# hamilton-thermostat-interface.net
KiCad netlist of a schematic drawn in EAGLE
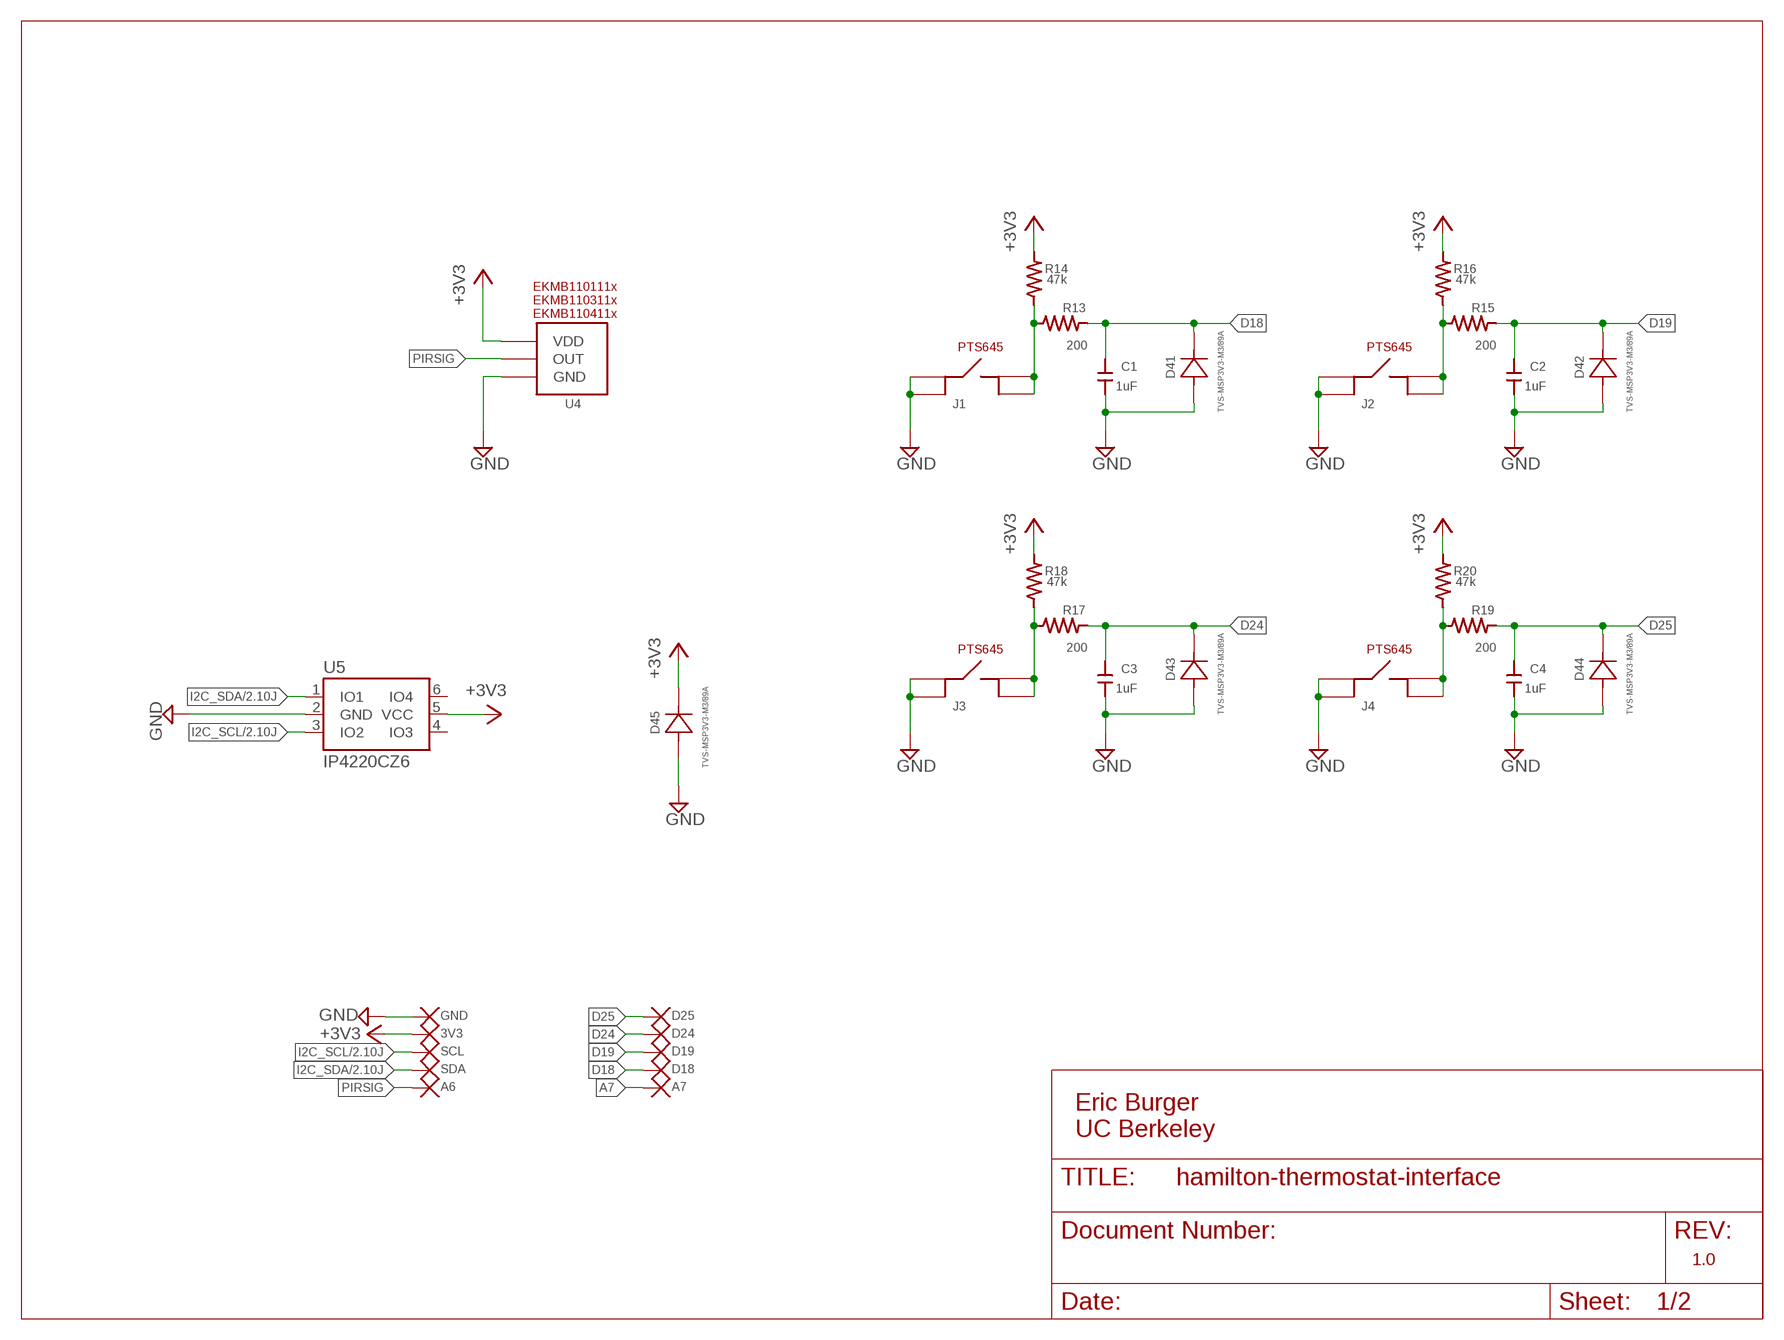
[diagram p0: schematic, sheet 1]
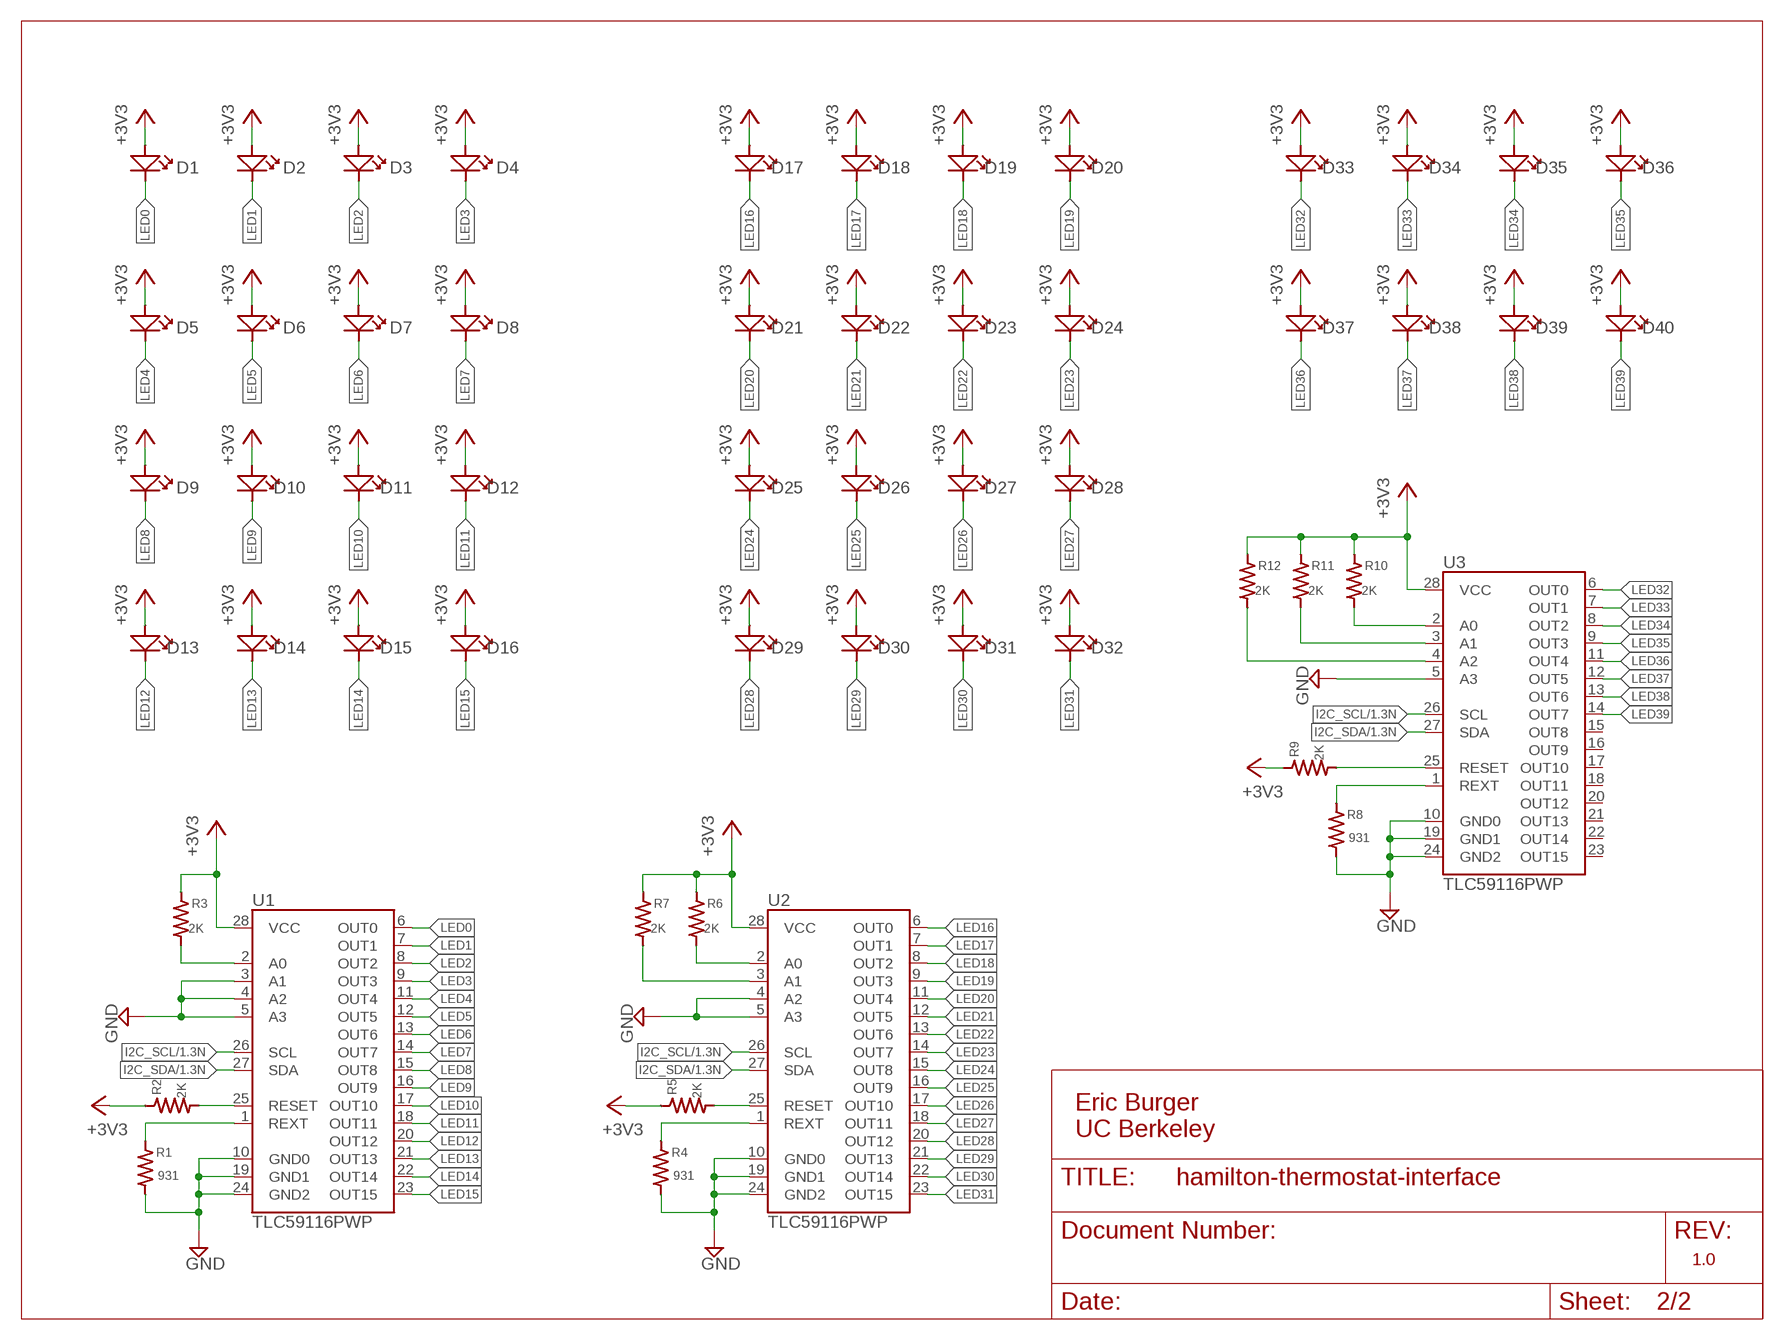
[diagram p1: schematic, sheet 2]

(export (version "E")
  (design (tool "Eeschema 10.0.6"))
  (components
    (comp (ref "C1")
      (value "1uF")
      (footprint "eagle-import:S0402")
      (libsource (lib "eagle-import") (part "0603_CAPACITORSMALL"))
    )
    (comp (ref "C2")
      (value "1uF")
      (footprint "eagle-import:S0402")
      (libsource (lib "eagle-import") (part "0603_CAPACITORSMALL"))
    )
    (comp (ref "C3")
      (value "1uF")
      (footprint "eagle-import:S0402")
      (libsource (lib "eagle-import") (part "0603_CAPACITORSMALL"))
    )
    (comp (ref "C4")
      (value "1uF")
      (footprint "eagle-import:S0402")
      (libsource (lib "eagle-import") (part "0603_CAPACITORSMALL"))
    )
    (comp (ref "D41")
      (value "TVS-MSP3V3-M3/89A")
      (footprint "eagle-import:DIODE_MSP3V3")
      (fields (field (name "MANUFACTURER_PART_NUMBER") "MSP3V3M389A"))
      (libsource (lib "eagle-import") (part "MSP3V3-M3/89A"))
    )
    (comp (ref "D42")
      (value "TVS-MSP3V3-M3/89A")
      (footprint "eagle-import:DIODE_MSP3V3")
      (fields (field (name "MANUFACTURER_PART_NUMBER") "MSP3V3M389A"))
      (libsource (lib "eagle-import") (part "MSP3V3-M3/89A"))
    )
    (comp (ref "D43")
      (value "TVS-MSP3V3-M3/89A")
      (footprint "eagle-import:DIODE_MSP3V3")
      (fields (field (name "MANUFACTURER_PART_NUMBER") "MSP3V3M389A"))
      (libsource (lib "eagle-import") (part "MSP3V3-M3/89A"))
    )
    (comp (ref "D44")
      (value "TVS-MSP3V3-M3/89A")
      (footprint "eagle-import:DIODE_MSP3V3")
      (fields (field (name "MANUFACTURER_PART_NUMBER") "MSP3V3M389A"))
      (libsource (lib "eagle-import") (part "MSP3V3-M3/89A"))
    )
    (comp (ref "D45")
      (value "TVS-MSP3V3-M3/89A")
      (footprint "eagle-import:DIODE_MSP3V3")
      (fields (field (name "MANUFACTURER_PART_NUMBER") "MSP3V3M389A"))
      (libsource (lib "eagle-import") (part "MSP3V3-M3/89A"))
    )
    (comp (ref "J1")
      (value "PTS645")
      (footprint "eagle-import:PTS645")
      (libsource (lib "eagle-import") (part "PTS645"))
    )
    (comp (ref "J2")
      (value "PTS645")
      (footprint "eagle-import:PTS645")
      (libsource (lib "eagle-import") (part "PTS645"))
    )
    (comp (ref "J3")
      (value "PTS645")
      (footprint "eagle-import:PTS645")
      (libsource (lib "eagle-import") (part "PTS645"))
    )
    (comp (ref "J4")
      (value "PTS645")
      (footprint "eagle-import:PTS645")
      (libsource (lib "eagle-import") (part "PTS645"))
    )
    (comp (ref "R13")
      (value "200")
      (footprint "eagle-import:S0402")
      (libsource (lib "eagle-import") (part "0603_RESISTORSMALL"))
    )
    (comp (ref "R14")
      (value "47k")
      (footprint "eagle-import:S0402")
      (libsource (lib "eagle-import") (part "0603_RESISTORSMALL"))
    )
    (comp (ref "R15")
      (value "200")
      (footprint "eagle-import:S0402")
      (libsource (lib "eagle-import") (part "0603_RESISTORSMALL"))
    )
    (comp (ref "R16")
      (value "47k")
      (footprint "eagle-import:S0402")
      (libsource (lib "eagle-import") (part "0603_RESISTORSMALL"))
    )
    (comp (ref "R17")
      (value "200")
      (footprint "eagle-import:S0402")
      (libsource (lib "eagle-import") (part "0603_RESISTORSMALL"))
    )
    (comp (ref "R18")
      (value "47k")
      (footprint "eagle-import:S0402")
      (libsource (lib "eagle-import") (part "0603_RESISTORSMALL"))
    )
    (comp (ref "R19")
      (value "200")
      (footprint "eagle-import:S0402")
      (libsource (lib "eagle-import") (part "0603_RESISTORSMALL"))
    )
    (comp (ref "R20")
      (value "47k")
      (footprint "eagle-import:S0402")
      (libsource (lib "eagle-import") (part "0603_RESISTORSMALL"))
    )
    (comp (ref "TP9")
      (value "SDA")
      (footprint "eagle-import:TPP")
      (libsource (lib "eagle-import") (part "TP"))
    )
    (comp (ref "TP10")
      (value "SCL")
      (footprint "eagle-import:TPP")
      (libsource (lib "eagle-import") (part "TP"))
    )
    (comp (ref "TP11")
      (value "3V3")
      (footprint "eagle-import:TPP")
      (libsource (lib "eagle-import") (part "TP"))
    )
    (comp (ref "TP12")
      (value "GND")
      (footprint "eagle-import:TPP")
      (libsource (lib "eagle-import") (part "TP"))
    )
    (comp (ref "TP14")
      (value "D25")
      (footprint "eagle-import:TPP")
      (libsource (lib "eagle-import") (part "TP"))
    )
    (comp (ref "TP15")
      (value "D24")
      (footprint "eagle-import:TPP")
      (libsource (lib "eagle-import") (part "TP"))
    )
    (comp (ref "TP16")
      (value "A6")
      (footprint "eagle-import:TPP")
      (libsource (lib "eagle-import") (part "TP"))
    )
    (comp (ref "TP17")
      (value "D18")
      (footprint "eagle-import:TPP")
      (libsource (lib "eagle-import") (part "TP"))
    )
    (comp (ref "TP18")
      (value "D19")
      (footprint "eagle-import:TPP")
      (libsource (lib "eagle-import") (part "TP"))
    )
    (comp (ref "TP19")
      (value "A7")
      (footprint "eagle-import:TPP")
      (libsource (lib "eagle-import") (part "TP"))
    )
    (comp (ref "U4")
      (value "PANASONIC_PIR")
      (footprint "eagle-import:PIR")
      (libsource (lib "eagle-import") (part "PANASONIC_PIR"))
    )
    (comp (ref "U5")
      (value "IP4220CZ6")
      (footprint "eagle-import:SOT23-6")
      (libsource (lib "eagle-import") (part "IP4220CZ6SOT-23"))
    )
    (comp (ref "D1")
      (value "DNP")
      (footprint "eagle-import:LINE_0603")
      (libsource (lib "eagle-import") (part "STATLEDLINE"))
    )
    (comp (ref "D2")
      (value "DNP")
      (footprint "eagle-import:LINE_0603")
      (libsource (lib "eagle-import") (part "STATLEDLINE"))
    )
    (comp (ref "D3")
      (value "DNP")
      (footprint "eagle-import:LINE_0603")
      (libsource (lib "eagle-import") (part "STATLEDLINE"))
    )
    (comp (ref "D4")
      (value "DNP")
      (footprint "eagle-import:LINE_0603")
      (libsource (lib "eagle-import") (part "STATLEDLINE"))
    )
    (comp (ref "D5")
      (value "DNP")
      (footprint "eagle-import:LINE_0603")
      (libsource (lib "eagle-import") (part "STATLEDLINE"))
    )
    (comp (ref "D6")
      (value "DNP")
      (footprint "eagle-import:LINE_0603")
      (libsource (lib "eagle-import") (part "STATLEDLINE"))
    )
    (comp (ref "D7")
      (value "DNP")
      (footprint "eagle-import:LINE_0603")
      (libsource (lib "eagle-import") (part "STATLEDLINE"))
    )
    (comp (ref "D8")
      (value "DNP")
      (footprint "eagle-import:LINE_0603")
      (libsource (lib "eagle-import") (part "STATLEDLINE"))
    )
    (comp (ref "D9")
      (value "DNP")
      (footprint "eagle-import:LINE_0603")
      (libsource (lib "eagle-import") (part "STATLEDLINE"))
    )
    (comp (ref "D10")
      (value "DNP")
      (footprint "eagle-import:LINE_0603")
      (libsource (lib "eagle-import") (part "STATLEDLINE"))
    )
    (comp (ref "D11")
      (value "DNP")
      (footprint "eagle-import:LINE_0603")
      (libsource (lib "eagle-import") (part "STATLEDLINE"))
    )
    (comp (ref "D12")
      (value "DNP")
      (footprint "eagle-import:LINE_0603")
      (libsource (lib "eagle-import") (part "STATLEDLINE"))
    )
    (comp (ref "D13")
      (value "DNP")
      (footprint "eagle-import:LINE_0603")
      (libsource (lib "eagle-import") (part "STATLEDLINE"))
    )
    (comp (ref "D14")
      (value "DNP")
      (footprint "eagle-import:LINE_0603")
      (libsource (lib "eagle-import") (part "STATLEDLINE"))
    )
    (comp (ref "D15")
      (value "DNP")
      (footprint "eagle-import:LINE_0603")
      (libsource (lib "eagle-import") (part "STATLEDLINE"))
    )
    (comp (ref "D16")
      (value "DNP")
      (footprint "eagle-import:LINE_0603")
      (libsource (lib "eagle-import") (part "STATLEDLINE"))
    )
    (comp (ref "D17")
      (value "DNP")
      (footprint "eagle-import:LINE_0603")
      (libsource (lib "eagle-import") (part "STATLEDLINE"))
    )
    (comp (ref "D18")
      (value "DNP")
      (footprint "eagle-import:LINE_0603")
      (libsource (lib "eagle-import") (part "STATLEDLINE"))
    )
    (comp (ref "D19")
      (value "DNP")
      (footprint "eagle-import:LINE_0603")
      (libsource (lib "eagle-import") (part "STATLEDLINE"))
    )
    (comp (ref "D20")
      (value "DNP")
      (footprint "eagle-import:LINE_0603")
      (libsource (lib "eagle-import") (part "STATLEDLINE"))
    )
    (comp (ref "D21")
      (value "DNP")
      (footprint "eagle-import:LINE_0603")
      (libsource (lib "eagle-import") (part "STATLEDLINE"))
    )
    (comp (ref "D22")
      (value "DNP")
      (footprint "eagle-import:LINE_0603")
      (libsource (lib "eagle-import") (part "STATLEDLINE"))
    )
    (comp (ref "D23")
      (value "DNP")
      (footprint "eagle-import:LINE_0603")
      (libsource (lib "eagle-import") (part "STATLEDLINE"))
    )
    (comp (ref "D24")
      (value "DNP")
      (footprint "eagle-import:LINE_0603")
      (libsource (lib "eagle-import") (part "STATLEDLINE"))
    )
    (comp (ref "D25")
      (value "DNP")
      (footprint "eagle-import:LINE_0603")
      (libsource (lib "eagle-import") (part "STATLEDLINE"))
    )
    (comp (ref "D26")
      (value "DNP")
      (footprint "eagle-import:LINE_0603")
      (libsource (lib "eagle-import") (part "STATLEDLINE"))
    )
    (comp (ref "D27")
      (value "DNP")
      (footprint "eagle-import:LINE_0603")
      (libsource (lib "eagle-import") (part "STATLEDLINE"))
    )
    (comp (ref "D28")
      (value "DNP")
      (footprint "eagle-import:LINE_0603")
      (libsource (lib "eagle-import") (part "STATLEDLINE"))
    )
    (comp (ref "D29")
      (value "DNP")
      (footprint "eagle-import:LINE_0603")
      (libsource (lib "eagle-import") (part "STATLEDLINE"))
    )
    (comp (ref "D30")
      (value "DNP")
      (footprint "eagle-import:LINE_0603")
      (libsource (lib "eagle-import") (part "STATLEDLINE"))
    )
    (comp (ref "D31")
      (value "DNP")
      (footprint "eagle-import:LINE_0603")
      (libsource (lib "eagle-import") (part "STATLEDLINE"))
    )
    (comp (ref "D32")
      (value "DNP")
      (footprint "eagle-import:LINE_0603")
      (libsource (lib "eagle-import") (part "STATLEDLINE"))
    )
    (comp (ref "D33")
      (value "DNP")
      (footprint "eagle-import:LINE_0603")
      (libsource (lib "eagle-import") (part "STATLEDLINE"))
    )
    (comp (ref "D34")
      (value "DNP")
      (footprint "eagle-import:LINE_0603")
      (libsource (lib "eagle-import") (part "STATLEDLINE"))
    )
    (comp (ref "D35")
      (value "DNP")
      (footprint "eagle-import:LINE_0603")
      (libsource (lib "eagle-import") (part "STATLEDLINE"))
    )
    (comp (ref "D36")
      (value "DNP")
      (footprint "eagle-import:LINE_0603")
      (libsource (lib "eagle-import") (part "STATLEDLINE"))
    )
    (comp (ref "D37")
      (value "DNP")
      (footprint "eagle-import:LINE_0603")
      (libsource (lib "eagle-import") (part "STATLEDLINE"))
    )
    (comp (ref "D38")
      (value "DNP")
      (footprint "eagle-import:LINE_0603")
      (libsource (lib "eagle-import") (part "STATLEDLINE"))
    )
    (comp (ref "D39")
      (value "DNP")
      (footprint "eagle-import:LINE_0603")
      (libsource (lib "eagle-import") (part "STATLEDLINE"))
    )
    (comp (ref "D40")
      (value "DNP")
      (footprint "eagle-import:LINE_0603")
      (libsource (lib "eagle-import") (part "STATLEDLINE"))
    )
    (comp (ref "R1")
      (value "931")
      (footprint "eagle-import:S0402")
      (libsource (lib "eagle-import") (part "0603_RESISTORSMALL"))
    )
    (comp (ref "R2")
      (value "2K")
      (footprint "eagle-import:S0402")
      (libsource (lib "eagle-import") (part "0603_RESISTORSMALL"))
    )
    (comp (ref "R3")
      (value "2K")
      (footprint "eagle-import:S0402")
      (libsource (lib "eagle-import") (part "0603_RESISTORSMALL"))
    )
    (comp (ref "R4")
      (value "931")
      (footprint "eagle-import:S0402")
      (libsource (lib "eagle-import") (part "0603_RESISTORSMALL"))
    )
    (comp (ref "R5")
      (value "2K")
      (footprint "eagle-import:S0402")
      (libsource (lib "eagle-import") (part "0603_RESISTORSMALL"))
    )
    (comp (ref "R6")
      (value "2K")
      (footprint "eagle-import:S0402")
      (libsource (lib "eagle-import") (part "0603_RESISTORSMALL"))
    )
    (comp (ref "R7")
      (value "2K")
      (footprint "eagle-import:S0402")
      (libsource (lib "eagle-import") (part "0603_RESISTORSMALL"))
    )
    (comp (ref "R8")
      (value "931")
      (footprint "eagle-import:S0402")
      (libsource (lib "eagle-import") (part "0603_RESISTORSMALL"))
    )
    (comp (ref "R9")
      (value "2K")
      (footprint "eagle-import:S0402")
      (libsource (lib "eagle-import") (part "0603_RESISTORSMALL"))
    )
    (comp (ref "R10")
      (value "2K")
      (footprint "eagle-import:S0402")
      (libsource (lib "eagle-import") (part "0603_RESISTORSMALL"))
    )
    (comp (ref "R11")
      (value "2K")
      (footprint "eagle-import:S0402")
      (libsource (lib "eagle-import") (part "0603_RESISTORSMALL"))
    )
    (comp (ref "R12")
      (value "2K")
      (footprint "eagle-import:S0402")
      (libsource (lib "eagle-import") (part "0603_RESISTORSMALL"))
    )
    (comp (ref "U1")
      (value "TLC59116PWP")
      (footprint "eagle-import:TSSOP28-GROUNDPAD")
      (libsource (lib "eagle-import") (part "TLC59116PWP"))
    )
    (comp (ref "U2")
      (value "TLC59116PWP")
      (footprint "eagle-import:TSSOP28-GROUNDPAD")
      (libsource (lib "eagle-import") (part "TLC59116PWP"))
    )
    (comp (ref "U3")
      (value "TLC59116PWP")
      (footprint "eagle-import:TSSOP28-GROUNDPAD")
      (libsource (lib "eagle-import") (part "TLC59116PWP"))
    )
  )
  (nets
    (net (code "1") (name "+3V3") (class "Default")
      (node (ref "D1") (pin "P") (pinfunction "+_P") (pintype "passive"))
      (node (ref "D10") (pin "P") (pinfunction "+_P") (pintype "passive"))
      (node (ref "D11") (pin "P") (pinfunction "+_P") (pintype "passive"))
      (node (ref "D12") (pin "P") (pinfunction "+_P") (pintype "passive"))
      (node (ref "D13") (pin "P") (pinfunction "+_P") (pintype "passive"))
      (node (ref "D14") (pin "P") (pinfunction "+_P") (pintype "passive"))
      (node (ref "D15") (pin "P") (pinfunction "+_P") (pintype "passive"))
      (node (ref "D16") (pin "P") (pinfunction "+_P") (pintype "passive"))
      (node (ref "D17") (pin "P") (pinfunction "+_P") (pintype "passive"))
      (node (ref "D18") (pin "P") (pinfunction "+_P") (pintype "passive"))
      (node (ref "D19") (pin "P") (pinfunction "+_P") (pintype "passive"))
      (node (ref "D2") (pin "P") (pinfunction "+_P") (pintype "passive"))
      (node (ref "D20") (pin "P") (pinfunction "+_P") (pintype "passive"))
      (node (ref "D21") (pin "P") (pinfunction "+_P") (pintype "passive"))
      (node (ref "D22") (pin "P") (pinfunction "+_P") (pintype "passive"))
      (node (ref "D23") (pin "P") (pinfunction "+_P") (pintype "passive"))
      (node (ref "D24") (pin "P") (pinfunction "+_P") (pintype "passive"))
      (node (ref "D25") (pin "P") (pinfunction "+_P") (pintype "passive"))
      (node (ref "D26") (pin "P") (pinfunction "+_P") (pintype "passive"))
      (node (ref "D27") (pin "P") (pinfunction "+_P") (pintype "passive"))
      (node (ref "D28") (pin "P") (pinfunction "+_P") (pintype "passive"))
      (node (ref "D29") (pin "P") (pinfunction "+_P") (pintype "passive"))
      (node (ref "D3") (pin "P") (pinfunction "+_P") (pintype "passive"))
      (node (ref "D30") (pin "P") (pinfunction "+_P") (pintype "passive"))
      (node (ref "D31") (pin "P") (pinfunction "+_P") (pintype "passive"))
      (node (ref "D32") (pin "P") (pinfunction "+_P") (pintype "passive"))
      (node (ref "D33") (pin "P") (pinfunction "+_P") (pintype "passive"))
      (node (ref "D34") (pin "P") (pinfunction "+_P") (pintype "passive"))
      (node (ref "D35") (pin "P") (pinfunction "+_P") (pintype "passive"))
      (node (ref "D36") (pin "P") (pinfunction "+_P") (pintype "passive"))
      (node (ref "D37") (pin "P") (pinfunction "+_P") (pintype "passive"))
      (node (ref "D38") (pin "P") (pinfunction "+_P") (pintype "passive"))
      (node (ref "D39") (pin "P") (pinfunction "+_P") (pintype "passive"))
      (node (ref "D4") (pin "P") (pinfunction "+_P") (pintype "passive"))
      (node (ref "D40") (pin "P") (pinfunction "+_P") (pintype "passive"))
      (node (ref "D45") (pin "1") (pinfunction "12_1") (pintype "passive"))
      (node (ref "D5") (pin "P") (pinfunction "+_P") (pintype "passive"))
      (node (ref "D6") (pin "P") (pinfunction "+_P") (pintype "passive"))
      (node (ref "D7") (pin "P") (pinfunction "+_P") (pintype "passive"))
      (node (ref "D8") (pin "P") (pinfunction "+_P") (pintype "passive"))
      (node (ref "D9") (pin "P") (pinfunction "+_P") (pintype "passive"))
      (node (ref "R10") (pin "P$2") (pinfunction "P$2_P$2") (pintype "passive"))
      (node (ref "R11") (pin "P$2") (pinfunction "P$2_P$2") (pintype "passive"))
      (node (ref "R12") (pin "P$2") (pinfunction "P$2_P$2") (pintype "passive"))
      (node (ref "R14") (pin "P$1") (pinfunction "P$1_P$1") (pintype "passive"))
      (node (ref "R16") (pin "P$1") (pinfunction "P$1_P$1") (pintype "passive"))
      (node (ref "R18") (pin "P$1") (pinfunction "P$1_P$1") (pintype "passive"))
      (node (ref "R2") (pin "P$2") (pinfunction "P$2_P$2") (pintype "passive"))
      (node (ref "R20") (pin "P$1") (pinfunction "P$1_P$1") (pintype "passive"))
      (node (ref "R3") (pin "P$2") (pinfunction "P$2_P$2") (pintype "passive"))
      (node (ref "R5") (pin "P$2") (pinfunction "P$2_P$2") (pintype "passive"))
      (node (ref "R6") (pin "P$2") (pinfunction "P$2_P$2") (pintype "passive"))
      (node (ref "R7") (pin "P$2") (pinfunction "P$2_P$2") (pintype "passive"))
      (node (ref "R9") (pin "P$2") (pinfunction "P$2_P$2") (pintype "passive"))
      (node (ref "TP11") (pin "P$1") (pinfunction "P$1_P$1") (pintype "bidirectional"))
      (node (ref "U1") (pin "28") (pinfunction "VCC_28") (pintype "bidirectional"))
      (node (ref "U2") (pin "28") (pinfunction "VCC_28") (pintype "bidirectional"))
      (node (ref "U3") (pin "28") (pinfunction "VCC_28") (pintype "bidirectional"))
      (node (ref "U4") (pin "VDD") (pinfunction "VDD_VDD") (pintype "bidirectional"))
      (node (ref "U5") (pin "5") (pinfunction "VCC_5") (pintype "bidirectional"))
    )
    (net (code "2") (name "A7") (class "Default")
      (node (ref "TP19") (pin "P$1") (pinfunction "P$1_P$1") (pintype "bidirectional"))
    )
    (net (code "3") (name "D18") (class "Default")
      (node (ref "C1") (pin "P$2") (pinfunction "P$2_P$2") (pintype "passive"))
      (node (ref "D41") (pin "1") (pinfunction "12_1") (pintype "passive"))
      (node (ref "R13") (pin "P$1") (pinfunction "P$1_P$1") (pintype "passive"))
      (node (ref "TP17") (pin "P$1") (pinfunction "P$1_P$1") (pintype "bidirectional"))
    )
    (net (code "4") (name "D19") (class "Default")
      (node (ref "C2") (pin "P$2") (pinfunction "P$2_P$2") (pintype "passive"))
      (node (ref "D42") (pin "1") (pinfunction "12_1") (pintype "passive"))
      (node (ref "R15") (pin "P$1") (pinfunction "P$1_P$1") (pintype "passive"))
      (node (ref "TP18") (pin "P$1") (pinfunction "P$1_P$1") (pintype "bidirectional"))
    )
    (net (code "5") (name "D24") (class "Default")
      (node (ref "C3") (pin "P$2") (pinfunction "P$2_P$2") (pintype "passive"))
      (node (ref "D43") (pin "1") (pinfunction "12_1") (pintype "passive"))
      (node (ref "R17") (pin "P$1") (pinfunction "P$1_P$1") (pintype "passive"))
      (node (ref "TP15") (pin "P$1") (pinfunction "P$1_P$1") (pintype "bidirectional"))
    )
    (net (code "6") (name "D25") (class "Default")
      (node (ref "C4") (pin "P$2") (pinfunction "P$2_P$2") (pintype "passive"))
      (node (ref "D44") (pin "1") (pinfunction "12_1") (pintype "passive"))
      (node (ref "R19") (pin "P$1") (pinfunction "P$1_P$1") (pintype "passive"))
      (node (ref "TP14") (pin "P$1") (pinfunction "P$1_P$1") (pintype "bidirectional"))
    )
    (net (code "7") (name "GND") (class "Default")
      (node (ref "C1") (pin "P$1") (pinfunction "P$1_P$1") (pintype "passive"))
      (node (ref "C2") (pin "P$1") (pinfunction "P$1_P$1") (pintype "passive"))
      (node (ref "C3") (pin "P$1") (pinfunction "P$1_P$1") (pintype "passive"))
      (node (ref "C4") (pin "P$1") (pinfunction "P$1_P$1") (pintype "passive"))
      (node (ref "D41") (pin "2") (pinfunction "21_2") (pintype "passive"))
      (node (ref "D42") (pin "2") (pinfunction "21_2") (pintype "passive"))
      (node (ref "D43") (pin "2") (pinfunction "21_2") (pintype "passive"))
      (node (ref "D44") (pin "2") (pinfunction "21_2") (pintype "passive"))
      (node (ref "D45") (pin "2") (pinfunction "21_2") (pintype "passive"))
      (node (ref "J1") (pin "3") (pinfunction "3_3") (pintype "bidirectional"))
      (node (ref "J1") (pin "4") (pinfunction "4_4") (pintype "bidirectional"))
      (node (ref "J2") (pin "3") (pinfunction "3_3") (pintype "bidirectional"))
      (node (ref "J2") (pin "4") (pinfunction "4_4") (pintype "bidirectional"))
      (node (ref "J3") (pin "3") (pinfunction "3_3") (pintype "bidirectional"))
      (node (ref "J3") (pin "4") (pinfunction "4_4") (pintype "bidirectional"))
      (node (ref "J4") (pin "3") (pinfunction "3_3") (pintype "bidirectional"))
      (node (ref "J4") (pin "4") (pinfunction "4_4") (pintype "bidirectional"))
      (node (ref "R1") (pin "P$1") (pinfunction "P$1_P$1") (pintype "passive"))
      (node (ref "R4") (pin "P$1") (pinfunction "P$1_P$1") (pintype "passive"))
      (node (ref "R8") (pin "P$1") (pinfunction "P$1_P$1") (pintype "passive"))
      (node (ref "TP12") (pin "P$1") (pinfunction "P$1_P$1") (pintype "bidirectional"))
      (node (ref "U1") (pin "10") (pinfunction "GND0_10") (pintype "bidirectional"))
      (node (ref "U1") (pin "19") (pinfunction "GND1_19") (pintype "bidirectional"))
      (node (ref "U1") (pin "24") (pinfunction "GND2_24") (pintype "bidirectional"))
      (node (ref "U1") (pin "3") (pinfunction "A1_3") (pintype "bidirectional"))
      (node (ref "U1") (pin "4") (pinfunction "A2_4") (pintype "bidirectional"))
      (node (ref "U1") (pin "5") (pinfunction "A3_5") (pintype "bidirectional"))
      (node (ref "U2") (pin "10") (pinfunction "GND0_10") (pintype "bidirectional"))
      (node (ref "U2") (pin "19") (pinfunction "GND1_19") (pintype "bidirectional"))
      (node (ref "U2") (pin "24") (pinfunction "GND2_24") (pintype "bidirectional"))
      (node (ref "U2") (pin "4") (pinfunction "A2_4") (pintype "bidirectional"))
      (node (ref "U2") (pin "5") (pinfunction "A3_5") (pintype "bidirectional"))
      (node (ref "U3") (pin "10") (pinfunction "GND0_10") (pintype "bidirectional"))
      (node (ref "U3") (pin "19") (pinfunction "GND1_19") (pintype "bidirectional"))
      (node (ref "U3") (pin "24") (pinfunction "GND2_24") (pintype "bidirectional"))
      (node (ref "U3") (pin "5") (pinfunction "A3_5") (pintype "bidirectional"))
      (node (ref "U4") (pin "GND") (pinfunction "GND_GND") (pintype "bidirectional"))
      (node (ref "U5") (pin "2") (pinfunction "GND_2") (pintype "bidirectional"))
    )
    (net (code "8") (name "I2C_SCL") (class "Default")
      (node (ref "TP10") (pin "P$1") (pinfunction "P$1_P$1") (pintype "bidirectional"))
      (node (ref "U1") (pin "26") (pinfunction "SCL_26") (pintype "bidirectional"))
      (node (ref "U2") (pin "26") (pinfunction "SCL_26") (pintype "bidirectional"))
      (node (ref "U3") (pin "26") (pinfunction "SCL_26") (pintype "bidirectional"))
      (node (ref "U5") (pin "3") (pinfunction "IO2_3") (pintype "bidirectional"))
    )
    (net (code "9") (name "I2C_SDA") (class "Default")
      (node (ref "TP9") (pin "P$1") (pinfunction "P$1_P$1") (pintype "bidirectional"))
      (node (ref "U1") (pin "27") (pinfunction "SDA_27") (pintype "bidirectional"))
      (node (ref "U2") (pin "27") (pinfunction "SDA_27") (pintype "bidirectional"))
      (node (ref "U3") (pin "27") (pinfunction "SDA_27") (pintype "bidirectional"))
      (node (ref "U5") (pin "1") (pinfunction "IO1_1") (pintype "bidirectional"))
    )
    (net (code "10") (name "LED0") (class "Default")
      (node (ref "D1") (pin "N") (pinfunction "-_N") (pintype "passive"))
      (node (ref "U1") (pin "6") (pinfunction "OUT0_6") (pintype "bidirectional"))
    )
    (net (code "11") (name "LED1") (class "Default")
      (node (ref "D2") (pin "N") (pinfunction "-_N") (pintype "passive"))
      (node (ref "U1") (pin "7") (pinfunction "OUT1_7") (pintype "bidirectional"))
    )
    (net (code "12") (name "LED2") (class "Default")
      (node (ref "D3") (pin "N") (pinfunction "-_N") (pintype "passive"))
      (node (ref "U1") (pin "8") (pinfunction "OUT2_8") (pintype "bidirectional"))
    )
    (net (code "13") (name "LED3") (class "Default")
      (node (ref "D4") (pin "N") (pinfunction "-_N") (pintype "passive"))
      (node (ref "U1") (pin "9") (pinfunction "OUT3_9") (pintype "bidirectional"))
    )
    (net (code "14") (name "LED4") (class "Default")
      (node (ref "D5") (pin "N") (pinfunction "-_N") (pintype "passive"))
      (node (ref "U1") (pin "11") (pinfunction "OUT4_11") (pintype "bidirectional"))
    )
    (net (code "15") (name "LED5") (class "Default")
      (node (ref "D6") (pin "N") (pinfunction "-_N") (pintype "passive"))
      (node (ref "U1") (pin "12") (pinfunction "OUT5_12") (pintype "bidirectional"))
    )
    (net (code "16") (name "LED6") (class "Default")
      (node (ref "D7") (pin "N") (pinfunction "-_N") (pintype "passive"))
      (node (ref "U1") (pin "13") (pinfunction "OUT6_13") (pintype "bidirectional"))
    )
    (net (code "17") (name "LED7") (class "Default")
      (node (ref "D8") (pin "N") (pinfunction "-_N") (pintype "passive"))
      (node (ref "U1") (pin "14") (pinfunction "OUT7_14") (pintype "bidirectional"))
    )
    (net (code "18") (name "LED8") (class "Default")
      (node (ref "D9") (pin "N") (pinfunction "-_N") (pintype "passive"))
      (node (ref "U1") (pin "15") (pinfunction "OUT8_15") (pintype "bidirectional"))
    )
    (net (code "19") (name "LED9") (class "Default")
      (node (ref "D10") (pin "N") (pinfunction "-_N") (pintype "passive"))
      (node (ref "U1") (pin "16") (pinfunction "OUT9_16") (pintype "bidirectional"))
    )
    (net (code "20") (name "LED10") (class "Default")
      (node (ref "D11") (pin "N") (pinfunction "-_N") (pintype "passive"))
      (node (ref "U1") (pin "17") (pinfunction "OUT10_17") (pintype "bidirectional"))
    )
    (net (code "21") (name "LED11") (class "Default")
      (node (ref "D12") (pin "N") (pinfunction "-_N") (pintype "passive"))
      (node (ref "U1") (pin "18") (pinfunction "OUT11_18") (pintype "bidirectional"))
    )
    (net (code "22") (name "LED12") (class "Default")
      (node (ref "D13") (pin "N") (pinfunction "-_N") (pintype "passive"))
      (node (ref "U1") (pin "20") (pinfunction "OUT12_20") (pintype "bidirectional"))
    )
    (net (code "23") (name "LED13") (class "Default")
      (node (ref "D14") (pin "N") (pinfunction "-_N") (pintype "passive"))
      (node (ref "U1") (pin "21") (pinfunction "OUT13_21") (pintype "bidirectional"))
    )
    (net (code "24") (name "LED14") (class "Default")
      (node (ref "D15") (pin "N") (pinfunction "-_N") (pintype "passive"))
      (node (ref "U1") (pin "22") (pinfunction "OUT14_22") (pintype "bidirectional"))
    )
    (net (code "25") (name "LED15") (class "Default")
      (node (ref "D16") (pin "N") (pinfunction "-_N") (pintype "passive"))
      (node (ref "U1") (pin "23") (pinfunction "OUT15_23") (pintype "bidirectional"))
    )
    (net (code "26") (name "LED16") (class "Default")
      (node (ref "D17") (pin "N") (pinfunction "-_N") (pintype "passive"))
      (node (ref "U2") (pin "6") (pinfunction "OUT0_6") (pintype "bidirectional"))
    )
    (net (code "27") (name "LED17") (class "Default")
      (node (ref "D18") (pin "N") (pinfunction "-_N") (pintype "passive"))
      (node (ref "U2") (pin "7") (pinfunction "OUT1_7") (pintype "bidirectional"))
    )
    (net (code "28") (name "LED18") (class "Default")
      (node (ref "D19") (pin "N") (pinfunction "-_N") (pintype "passive"))
      (node (ref "U2") (pin "8") (pinfunction "OUT2_8") (pintype "bidirectional"))
    )
    (net (code "29") (name "LED19") (class "Default")
      (node (ref "D20") (pin "N") (pinfunction "-_N") (pintype "passive"))
      (node (ref "U2") (pin "9") (pinfunction "OUT3_9") (pintype "bidirectional"))
    )
    (net (code "30") (name "LED20") (class "Default")
      (node (ref "D21") (pin "N") (pinfunction "-_N") (pintype "passive"))
      (node (ref "U2") (pin "11") (pinfunction "OUT4_11") (pintype "bidirectional"))
    )
    (net (code "31") (name "LED21") (class "Default")
      (node (ref "D22") (pin "N") (pinfunction "-_N") (pintype "passive"))
      (node (ref "U2") (pin "12") (pinfunction "OUT5_12") (pintype "bidirectional"))
    )
    (net (code "32") (name "LED22") (class "Default")
      (node (ref "D23") (pin "N") (pinfunction "-_N") (pintype "passive"))
      (node (ref "U2") (pin "13") (pinfunction "OUT6_13") (pintype "bidirectional"))
    )
    (net (code "33") (name "LED23") (class "Default")
      (node (ref "D24") (pin "N") (pinfunction "-_N") (pintype "passive"))
      (node (ref "U2") (pin "14") (pinfunction "OUT7_14") (pintype "bidirectional"))
    )
    (net (code "34") (name "LED24") (class "Default")
      (node (ref "D25") (pin "N") (pinfunction "-_N") (pintype "passive"))
      (node (ref "U2") (pin "15") (pinfunction "OUT8_15") (pintype "bidirectional"))
    )
    (net (code "35") (name "LED25") (class "Default")
      (node (ref "D26") (pin "N") (pinfunction "-_N") (pintype "passive"))
      (node (ref "U2") (pin "16") (pinfunction "OUT9_16") (pintype "bidirectional"))
    )
    (net (code "36") (name "LED26") (class "Default")
      (node (ref "D27") (pin "N") (pinfunction "-_N") (pintype "passive"))
      (node (ref "U2") (pin "17") (pinfunction "OUT10_17") (pintype "bidirectional"))
    )
    (net (code "37") (name "LED27") (class "Default")
      (node (ref "D28") (pin "N") (pinfunction "-_N") (pintype "passive"))
      (node (ref "U2") (pin "18") (pinfunction "OUT11_18") (pintype "bidirectional"))
    )
    (net (code "38") (name "LED28") (class "Default")
      (node (ref "D29") (pin "N") (pinfunction "-_N") (pintype "passive"))
      (node (ref "U2") (pin "20") (pinfunction "OUT12_20") (pintype "bidirectional"))
    )
    (net (code "39") (name "LED29") (class "Default")
      (node (ref "D30") (pin "N") (pinfunction "-_N") (pintype "passive"))
      (node (ref "U2") (pin "21") (pinfunction "OUT13_21") (pintype "bidirectional"))
    )
    (net (code "40") (name "LED30") (class "Default")
      (node (ref "D31") (pin "N") (pinfunction "-_N") (pintype "passive"))
      (node (ref "U2") (pin "22") (pinfunction "OUT14_22") (pintype "bidirectional"))
    )
    (net (code "41") (name "LED31") (class "Default")
      (node (ref "D32") (pin "N") (pinfunction "-_N") (pintype "passive"))
      (node (ref "U2") (pin "23") (pinfunction "OUT15_23") (pintype "bidirectional"))
    )
    (net (code "42") (name "LED32") (class "Default")
      (node (ref "D33") (pin "N") (pinfunction "-_N") (pintype "passive"))
      (node (ref "U3") (pin "6") (pinfunction "OUT0_6") (pintype "bidirectional"))
    )
    (net (code "43") (name "LED33") (class "Default")
      (node (ref "D34") (pin "N") (pinfunction "-_N") (pintype "passive"))
      (node (ref "U3") (pin "7") (pinfunction "OUT1_7") (pintype "bidirectional"))
    )
    (net (code "44") (name "LED34") (class "Default")
      (node (ref "D35") (pin "N") (pinfunction "-_N") (pintype "passive"))
      (node (ref "U3") (pin "8") (pinfunction "OUT2_8") (pintype "bidirectional"))
    )
    (net (code "45") (name "LED35") (class "Default")
      (node (ref "D36") (pin "N") (pinfunction "-_N") (pintype "passive"))
      (node (ref "U3") (pin "9") (pinfunction "OUT3_9") (pintype "bidirectional"))
    )
    (net (code "46") (name "LED36") (class "Default")
      (node (ref "D37") (pin "N") (pinfunction "-_N") (pintype "passive"))
      (node (ref "U3") (pin "11") (pinfunction "OUT4_11") (pintype "bidirectional"))
    )
    (net (code "47") (name "LED37") (class "Default")
      (node (ref "D38") (pin "N") (pinfunction "-_N") (pintype "passive"))
      (node (ref "U3") (pin "12") (pinfunction "OUT5_12") (pintype "bidirectional"))
    )
    (net (code "48") (name "LED38") (class "Default")
      (node (ref "D39") (pin "N") (pinfunction "-_N") (pintype "passive"))
      (node (ref "U3") (pin "13") (pinfunction "OUT6_13") (pintype "bidirectional"))
    )
    (net (code "49") (name "LED39") (class "Default")
      (node (ref "D40") (pin "N") (pinfunction "-_N") (pintype "passive"))
      (node (ref "U3") (pin "14") (pinfunction "OUT7_14") (pintype "bidirectional"))
    )
    (net (code "50") (name "Net-(J1-Pad1)") (class "Default")
      (node (ref "J1") (pin "1") (pinfunction "1_1") (pintype "bidirectional"))
      (node (ref "J1") (pin "2") (pinfunction "2_2") (pintype "bidirectional"))
      (node (ref "R13") (pin "P$2") (pinfunction "P$2_P$2") (pintype "passive"))
      (node (ref "R14") (pin "P$2") (pinfunction "P$2_P$2") (pintype "passive"))
    )
    (net (code "51") (name "Net-(J2-Pad1)") (class "Default")
      (node (ref "J2") (pin "1") (pinfunction "1_1") (pintype "bidirectional"))
      (node (ref "J2") (pin "2") (pinfunction "2_2") (pintype "bidirectional"))
      (node (ref "R15") (pin "P$2") (pinfunction "P$2_P$2") (pintype "passive"))
      (node (ref "R16") (pin "P$2") (pinfunction "P$2_P$2") (pintype "passive"))
    )
    (net (code "52") (name "Net-(J3-Pad1)") (class "Default")
      (node (ref "J3") (pin "1") (pinfunction "1_1") (pintype "bidirectional"))
      (node (ref "J3") (pin "2") (pinfunction "2_2") (pintype "bidirectional"))
      (node (ref "R17") (pin "P$2") (pinfunction "P$2_P$2") (pintype "passive"))
      (node (ref "R18") (pin "P$2") (pinfunction "P$2_P$2") (pintype "passive"))
    )
    (net (code "53") (name "Net-(J4-Pad1)") (class "Default")
      (node (ref "J4") (pin "1") (pinfunction "1_1") (pintype "bidirectional"))
      (node (ref "J4") (pin "2") (pinfunction "2_2") (pintype "bidirectional"))
      (node (ref "R19") (pin "P$2") (pinfunction "P$2_P$2") (pintype "passive"))
      (node (ref "R20") (pin "P$2") (pinfunction "P$2_P$2") (pintype "passive"))
    )
    (net (code "54") (name "Net-(U1-A0)") (class "Default")
      (node (ref "R3") (pin "P$1") (pinfunction "P$1_P$1") (pintype "passive"))
      (node (ref "U1") (pin "2") (pinfunction "A0_2") (pintype "bidirectional"))
    )
    (net (code "55") (name "Net-(U1-RESET)") (class "Default")
      (node (ref "R2") (pin "P$1") (pinfunction "P$1_P$1") (pintype "passive"))
      (node (ref "U1") (pin "25") (pinfunction "RESET_25") (pintype "bidirectional"))
    )
    (net (code "56") (name "Net-(U1-REXT)") (class "Default")
      (node (ref "R1") (pin "P$2") (pinfunction "P$2_P$2") (pintype "passive"))
      (node (ref "U1") (pin "1") (pinfunction "REXT_1") (pintype "bidirectional"))
    )
    (net (code "57") (name "Net-(U2-A0)") (class "Default")
      (node (ref "R6") (pin "P$1") (pinfunction "P$1_P$1") (pintype "passive"))
      (node (ref "U2") (pin "2") (pinfunction "A0_2") (pintype "bidirectional"))
    )
    (net (code "58") (name "Net-(U2-A1)") (class "Default")
      (node (ref "R7") (pin "P$1") (pinfunction "P$1_P$1") (pintype "passive"))
      (node (ref "U2") (pin "3") (pinfunction "A1_3") (pintype "bidirectional"))
    )
    (net (code "59") (name "Net-(U2-RESET)") (class "Default")
      (node (ref "R5") (pin "P$1") (pinfunction "P$1_P$1") (pintype "passive"))
      (node (ref "U2") (pin "25") (pinfunction "RESET_25") (pintype "bidirectional"))
    )
    (net (code "60") (name "Net-(U2-REXT)") (class "Default")
      (node (ref "R4") (pin "P$2") (pinfunction "P$2_P$2") (pintype "passive"))
      (node (ref "U2") (pin "1") (pinfunction "REXT_1") (pintype "bidirectional"))
    )
    (net (code "61") (name "Net-(U3-A0)") (class "Default")
      (node (ref "R10") (pin "P$1") (pinfunction "P$1_P$1") (pintype "passive"))
      (node (ref "U3") (pin "2") (pinfunction "A0_2") (pintype "bidirectional"))
    )
    (net (code "62") (name "Net-(U3-A1)") (class "Default")
      (node (ref "R11") (pin "P$1") (pinfunction "P$1_P$1") (pintype "passive"))
      (node (ref "U3") (pin "3") (pinfunction "A1_3") (pintype "bidirectional"))
    )
    (net (code "63") (name "Net-(U3-A2)") (class "Default")
      (node (ref "R12") (pin "P$1") (pinfunction "P$1_P$1") (pintype "passive"))
      (node (ref "U3") (pin "4") (pinfunction "A2_4") (pintype "bidirectional"))
    )
    (net (code "64") (name "Net-(U3-RESET)") (class "Default")
      (node (ref "R9") (pin "P$1") (pinfunction "P$1_P$1") (pintype "passive"))
      (node (ref "U3") (pin "25") (pinfunction "RESET_25") (pintype "bidirectional"))
    )
    (net (code "65") (name "Net-(U3-REXT)") (class "Default")
      (node (ref "R8") (pin "P$2") (pinfunction "P$2_P$2") (pintype "passive"))
      (node (ref "U3") (pin "1") (pinfunction "REXT_1") (pintype "bidirectional"))
    )
    (net (code "66") (name "PIRSIG") (class "Default")
      (node (ref "TP16") (pin "P$1") (pinfunction "P$1_P$1") (pintype "bidirectional"))
      (node (ref "U4") (pin "OUT") (pinfunction "OUT_OUT") (pintype "bidirectional"))
    )
    (net (code "67") (name "unconnected-(U3-OUT8-Pad15)") (class "Default")
      (node (ref "U3") (pin "15") (pinfunction "OUT8_15") (pintype "bidirectional"))
    )
    (net (code "68") (name "unconnected-(U3-OUT9-Pad16)") (class "Default")
      (node (ref "U3") (pin "16") (pinfunction "OUT9_16") (pintype "bidirectional"))
    )
    (net (code "69") (name "unconnected-(U3-OUT10-Pad17)") (class "Default")
      (node (ref "U3") (pin "17") (pinfunction "OUT10_17") (pintype "bidirectional"))
    )
    (net (code "70") (name "unconnected-(U3-OUT11-Pad18)") (class "Default")
      (node (ref "U3") (pin "18") (pinfunction "OUT11_18") (pintype "bidirectional"))
    )
    (net (code "71") (name "unconnected-(U3-OUT12-Pad20)") (class "Default")
      (node (ref "U3") (pin "20") (pinfunction "OUT12_20") (pintype "bidirectional"))
    )
    (net (code "72") (name "unconnected-(U3-OUT13-Pad21)") (class "Default")
      (node (ref "U3") (pin "21") (pinfunction "OUT13_21") (pintype "bidirectional"))
    )
    (net (code "73") (name "unconnected-(U3-OUT14-Pad22)") (class "Default")
      (node (ref "U3") (pin "22") (pinfunction "OUT14_22") (pintype "bidirectional"))
    )
    (net (code "74") (name "unconnected-(U3-OUT15-Pad23)") (class "Default")
      (node (ref "U3") (pin "23") (pinfunction "OUT15_23") (pintype "bidirectional"))
    )
    (net (code "75") (name "unconnected-(U5-IO3-Pad4)") (class "Default")
      (node (ref "U5") (pin "4") (pinfunction "IO3_4") (pintype "bidirectional"))
    )
    (net (code "76") (name "unconnected-(U5-IO4-Pad6)") (class "Default")
      (node (ref "U5") (pin "6") (pinfunction "IO4_6") (pintype "bidirectional"))
    )
  )
)
